# RGB.net
KiCad netlist of a schematic drawn in EAGLE
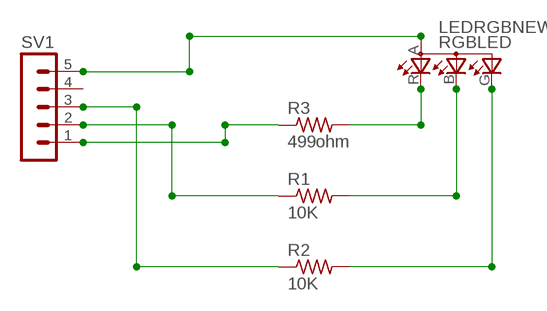
[diagram p0: schematic, sheet 1]

(export (version "E")
  (design (tool "Eeschema 10.0.6"))
  (components
    (comp (ref "R1")
      (value "10K")
      (footprint "eagle-import:R1206FAB")
      (libsource (lib "eagle-import") (part "RES-US1206FAB"))
    )
    (comp (ref "R2")
      (value "10K")
      (footprint "eagle-import:R1206FAB")
      (libsource (lib "eagle-import") (part "RES-US1206FAB"))
    )
    (comp (ref "R3")
      (value "499ohm")
      (footprint "eagle-import:R1206FAB")
      (libsource (lib "eagle-import") (part "RES-US1206FAB"))
    )
    (comp (ref "RGBLED")
      (value "LEDRGBNEW")
      (footprint "eagle-import:P-LCC-4")
      (libsource (lib "eagle-import") (part "LEDRGBNEW"))
    )
    (comp (ref "SV1")
      (value "MA05-1")
      (footprint "eagle-import:MA05-1")
      (libsource (lib "eagle-import") (part "MA05-1"))
    )
  )
  (nets
    (net (code "1") (name "Net-(R1-Pad1)") (class "Default")
      (node (ref "R1") (pin "1") (pinfunction "1_1") (pintype "passive"))
      (node (ref "SV1") (pin "2") (pinfunction "2_2") (pintype "passive"))
    )
    (net (code "2") (name "Net-(R2-Pad1)") (class "Default")
      (node (ref "R2") (pin "1") (pinfunction "1_1") (pintype "passive"))
      (node (ref "SV1") (pin "3") (pinfunction "3_3") (pintype "passive"))
    )
    (net (code "3") (name "Net-(R3-Pad1)") (class "Default")
      (node (ref "R3") (pin "1") (pinfunction "1_1") (pintype "passive"))
      (node (ref "SV1") (pin "1") (pinfunction "1_1") (pintype "passive"))
    )
    (net (code "4") (name "Net-(RGBLED-A2)") (class "Default")
      (node (ref "RGBLED") (pin "A") (pinfunction "A2_A") (pintype "passive"))
      (node (ref "SV1") (pin "5") (pinfunction "5_5") (pintype "passive"))
    )
    (net (code "5") (name "Net-(RGBLED-CBLUE)") (class "Default")
      (node (ref "R1") (pin "2") (pinfunction "2_2") (pintype "passive"))
      (node (ref "RGBLED") (pin "B") (pinfunction "CBLUE_B") (pintype "passive"))
    )
    (net (code "6") (name "Net-(RGBLED-CGREEN)") (class "Default")
      (node (ref "R2") (pin "2") (pinfunction "2_2") (pintype "passive"))
      (node (ref "RGBLED") (pin "G") (pinfunction "CGREEN_G") (pintype "passive"))
    )
    (net (code "7") (name "Net-(RGBLED-CRED)") (class "Default")
      (node (ref "R3") (pin "2") (pinfunction "2_2") (pintype "passive"))
      (node (ref "RGBLED") (pin "R") (pinfunction "CRED_R") (pintype "passive"))
    )
    (net (code "8") (name "unconnected-(SV1-Pad4)") (class "Default")
      (node (ref "SV1") (pin "4") (pinfunction "4_4") (pintype "passive"))
    )
  )
)
